# tick-box-1591A-mk-2_0.net
KiCad netlist of a schematic drawn in EAGLE
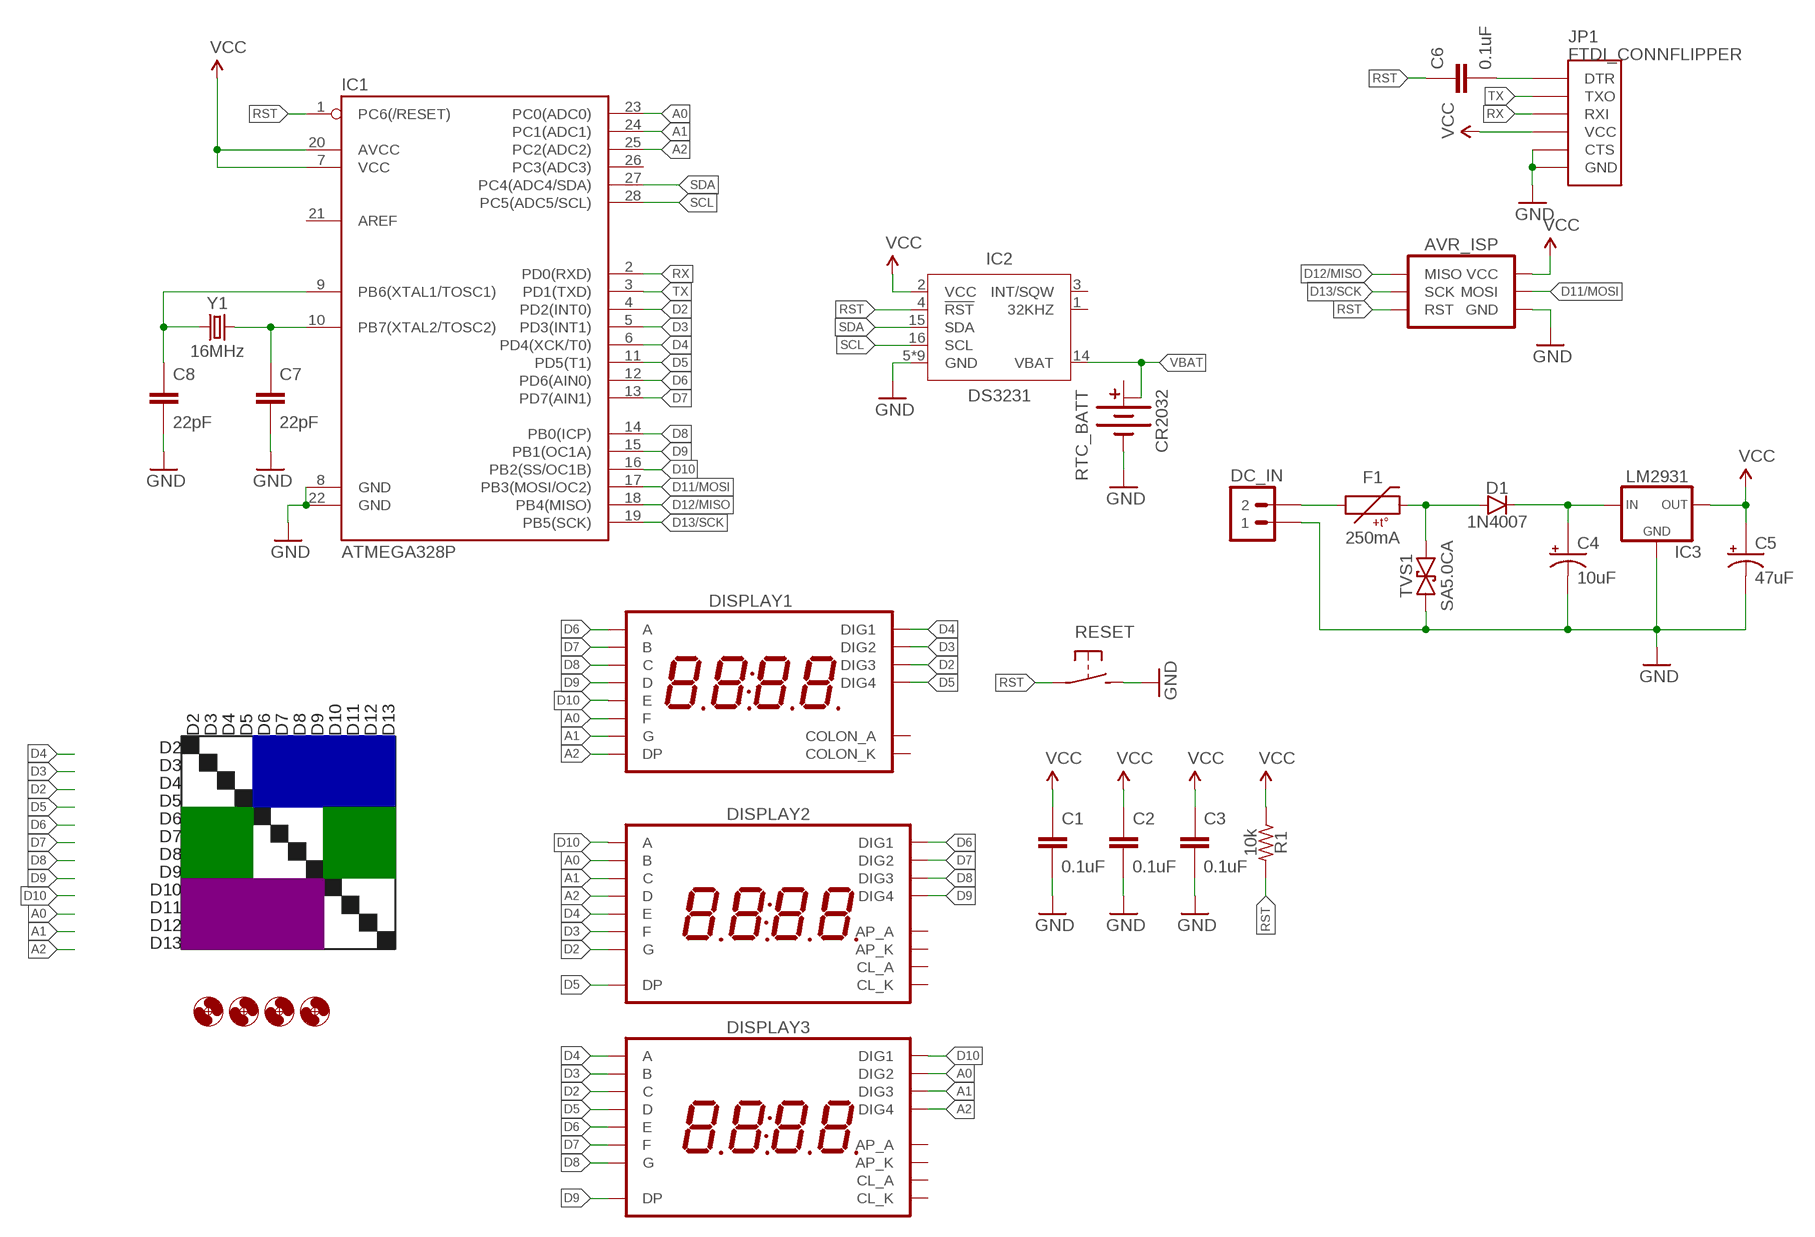
[diagram p0: schematic, sheet 1]

(export (version "E")
  (design (tool "Eeschema 10.0.6"))
  (components
    (comp (ref "AVR_ISP")
      (value "AVR_SPI_PRG_6PTH")
      (footprint "eagle-import:2X3")
      (libsource (lib "eagle-import") (part "AVR_SPI_PRG_6PTH"))
    )
    (comp (ref "C1")
      (value "0.1uF")
      (footprint "eagle-import:C025-024X044")
      (libsource (lib "eagle-import") (part "CAPACITOR-CERAMIC025-024X044"))
    )
    (comp (ref "C2")
      (value "0.1uF")
      (footprint "eagle-import:C025-024X044")
      (libsource (lib "eagle-import") (part "CAPACITOR-CERAMIC025-024X044"))
    )
    (comp (ref "C3")
      (value "0.1uF")
      (footprint "eagle-import:C025-024X044")
      (libsource (lib "eagle-import") (part "CAPACITOR-CERAMIC025-024X044"))
    )
    (comp (ref "C4")
      (value "10uF")
      (footprint "eagle-import:E2-4")
      (libsource (lib "eagle-import") (part "CAPACITOR-POLARIZEDE2-4"))
    )
    (comp (ref "C5")
      (value "47uF")
      (footprint "eagle-import:E2-4")
      (libsource (lib "eagle-import") (part "CAPACITOR-POLARIZEDE2-4"))
    )
    (comp (ref "C6")
      (value "0.1uF")
      (footprint "eagle-import:C025-024X044")
      (libsource (lib "eagle-import") (part "CAPACITOR-CERAMIC025-024X044"))
    )
    (comp (ref "C7")
      (value "22pF")
      (footprint "eagle-import:C025-024X044")
      (libsource (lib "eagle-import") (part "CAPACITOR-CERAMIC025-024X044"))
    )
    (comp (ref "C8")
      (value "22pF")
      (footprint "eagle-import:C025-024X044")
      (libsource (lib "eagle-import") (part "CAPACITOR-CERAMIC025-024X044"))
    )
    (comp (ref "D1")
      (value "1N4007")
      (footprint "eagle-import:DIODE-10.16MM")
      (libsource (lib "eagle-import") (part "DIODEPTH-10.68MM"))
    )
    (comp (ref "DC_IN")
      (value "M02PTH")
      (footprint "eagle-import:1X02")
      (libsource (lib "eagle-import") (part "M02PTH"))
    )
    (comp (ref "DISPLAY1")
      (value "7SEG_4DIGIT_COLON14.2MM-CC-NS")
      (footprint "eagle-import:7SEG_4DIG_NS")
      (libsource (lib "eagle-import") (part "7SEG_4DIGIT_COLON14.2MM-CC-NS"))
    )
    (comp (ref "DISPLAY2")
      (value "7SEG_4DIGIT_COLON_APOS")
      (footprint "eagle-import:7SEG_4DIG_10MM")
      (libsource (lib "eagle-import") (part "7SEG_4DIGIT_COLON_APOS"))
    )
    (comp (ref "DISPLAY3")
      (value "7SEG_4DIGIT_COLON_APOS")
      (footprint "eagle-import:7SEG_4DIG_10MM")
      (libsource (lib "eagle-import") (part "7SEG_4DIGIT_COLON_APOS"))
    )
    (comp (ref "F1")
      (value "250mA")
      (footprint "eagle-import:PTC-1206")
      (libsource (lib "eagle-import") (part "PTCSMD"))
    )
    (comp (ref "H1")
      (value "HOLE#2")
      (footprint "eagle-import:HOLE-#2")
      (libsource (lib "eagle-import") (part "HOLE#2"))
    )
    (comp (ref "H2")
      (value "HOLE#2")
      (footprint "eagle-import:HOLE-#2")
      (libsource (lib "eagle-import") (part "HOLE#2"))
    )
    (comp (ref "H3")
      (value "HOLE#2")
      (footprint "eagle-import:HOLE-#2")
      (libsource (lib "eagle-import") (part "HOLE#2"))
    )
    (comp (ref "H4")
      (value "HOLE#2")
      (footprint "eagle-import:HOLE-#2")
      (libsource (lib "eagle-import") (part "HOLE#2"))
    )
    (comp (ref "IC1")
      (value "ATMEGA328P")
      (footprint "eagle-import:DIL28-3")
      (libsource (lib "eagle-import") (part "ATMEGA328P_PDIP"))
    )
    (comp (ref "IC2")
      (value "DS3231")
      (footprint "eagle-import:SO16W")
      (libsource (lib "eagle-import") (part "DS3231"))
    )
    (comp (ref "IC3")
      (value "LM2931")
      (footprint "eagle-import:TO-92-AMMO")
      (libsource (lib "eagle-import") (part "V_REG_78XXTO-92-INLINE"))
    )
    (comp (ref "JP1")
      (value "FTDI_CONNFLIPPER")
      (footprint "eagle-import:FTDI_CONN_FLIP")
      (libsource (lib "eagle-import") (part "FTDI_CONNFLIPPER"))
    )
    (comp (ref "R1")
      (value "10k")
      (footprint "eagle-import:RESISTOR-AXIAL-PTH-6.35MM")
      (libsource (lib "eagle-import") (part "RESISTORPTH-AXIAL-6.35MM"))
    )
    (comp (ref "RESET")
      (value "SPST-NO-TACT3MM-PTH-SMALL-PADS")
      (footprint "eagle-import:DTS-3-SMALL-PADS")
      (libsource (lib "eagle-import") (part "SPST-NO-TACT3MM-PTH-SMALL-PADS"))
    )
    (comp (ref "RTC_BATT")
      (value "CR2032")
      (footprint "eagle-import:BATTCON_20MM_MINE")
      (libsource (lib "eagle-import") (part "BATTERY-COINCR2032_SMD"))
    )
    (comp (ref "TVS1")
      (value "SA5.0CA")
      (footprint "eagle-import:DO-41-TVS-BI-10.16MM")
      (libsource (lib "eagle-import") (part "TVSDO-41-10.16MM"))
    )
    (comp (ref "Y1")
      (value "16MHz")
      (footprint "eagle-import:HC49U-V")
      (libsource (lib "eagle-import") (part "CRYSTALHC49UV"))
    )
  )
  (nets
    (net (code "1") (name "A0") (class "Default")
      (node (ref "DISPLAY1") (pin "P$12") (pinfunction "F_P$12") (pintype "passive"))
      (node (ref "DISPLAY2") (pin "16") (pinfunction "B_16") (pintype "passive"))
      (node (ref "DISPLAY3") (pin "2") (pinfunction "DIG2_2") (pintype "passive"))
      (node (ref "IC1") (pin "23") (pinfunction "PC0(ADC0)_23") (pintype "bidirectional"))
    )
    (net (code "2") (name "A1") (class "Default")
      (node (ref "DISPLAY1") (pin "P$5") (pinfunction "G_P$5") (pintype "passive"))
      (node (ref "DISPLAY2") (pin "13") (pinfunction "C_13") (pintype "passive"))
      (node (ref "DISPLAY3") (pin "6") (pinfunction "DIG3_6") (pintype "passive"))
      (node (ref "IC1") (pin "24") (pinfunction "PC1(ADC1)_24") (pintype "bidirectional"))
    )
    (net (code "3") (name "A2") (class "Default")
      (node (ref "DISPLAY1") (pin "P$3") (pinfunction "DP_P$3") (pintype "passive"))
      (node (ref "DISPLAY2") (pin "3") (pinfunction "D_3") (pintype "passive"))
      (node (ref "DISPLAY3") (pin "8") (pinfunction "DIG4_8") (pintype "passive"))
      (node (ref "IC1") (pin "25") (pinfunction "PC2(ADC2)_25") (pintype "bidirectional"))
    )
    (net (code "4") (name "D2") (class "Default")
      (node (ref "DISPLAY1") (pin "P$10") (pinfunction "DIG3_P$10") (pintype "passive"))
      (node (ref "DISPLAY2") (pin "15") (pinfunction "G_15") (pintype "passive"))
      (node (ref "DISPLAY3") (pin "13") (pinfunction "C_13") (pintype "passive"))
      (node (ref "IC1") (pin "4") (pinfunction "PD2(INT0)_4") (pintype "bidirectional"))
    )
    (net (code "5") (name "D3") (class "Default")
      (node (ref "DISPLAY1") (pin "P$11") (pinfunction "DIG2_P$11") (pintype "passive"))
      (node (ref "DISPLAY2") (pin "11") (pinfunction "F_11") (pintype "passive"))
      (node (ref "DISPLAY3") (pin "16") (pinfunction "B_16") (pintype "passive"))
      (node (ref "IC1") (pin "5") (pinfunction "PD3(INT1)_5") (pintype "bidirectional"))
    )
    (net (code "6") (name "D4") (class "Default")
      (node (ref "DISPLAY1") (pin "P$14") (pinfunction "DIG1_P$14") (pintype "passive"))
      (node (ref "DISPLAY2") (pin "5") (pinfunction "E_5") (pintype "passive"))
      (node (ref "DISPLAY3") (pin "14") (pinfunction "A_14") (pintype "passive"))
      (node (ref "IC1") (pin "6") (pinfunction "PD4(XCK/T0)_6") (pintype "bidirectional"))
    )
    (net (code "7") (name "D5") (class "Default")
      (node (ref "DISPLAY1") (pin "P$6") (pinfunction "DIG4_P$6") (pintype "passive"))
      (node (ref "DISPLAY2") (pin "7") (pinfunction "DP_7") (pintype "passive"))
      (node (ref "DISPLAY3") (pin "3") (pinfunction "D_3") (pintype "passive"))
      (node (ref "IC1") (pin "11") (pinfunction "PD5(T1)_11") (pintype "bidirectional"))
    )
    (net (code "8") (name "D6") (class "Default")
      (node (ref "DISPLAY1") (pin "P$13") (pinfunction "A_P$13") (pintype "passive"))
      (node (ref "DISPLAY2") (pin "1") (pinfunction "DIG1_1") (pintype "passive"))
      (node (ref "DISPLAY3") (pin "5") (pinfunction "E_5") (pintype "passive"))
      (node (ref "IC1") (pin "12") (pinfunction "PD6(AIN0)_12") (pintype "bidirectional"))
    )
    (net (code "9") (name "D7") (class "Default")
      (node (ref "DISPLAY1") (pin "P$9") (pinfunction "B_P$9") (pintype "passive"))
      (node (ref "DISPLAY2") (pin "2") (pinfunction "DIG2_2") (pintype "passive"))
      (node (ref "DISPLAY3") (pin "11") (pinfunction "F_11") (pintype "passive"))
      (node (ref "IC1") (pin "13") (pinfunction "PD7(AIN1)_13") (pintype "bidirectional"))
    )
    (net (code "10") (name "D8") (class "Default")
      (node (ref "DISPLAY1") (pin "P$4") (pinfunction "C_P$4") (pintype "passive"))
      (node (ref "DISPLAY2") (pin "6") (pinfunction "DIG3_6") (pintype "passive"))
      (node (ref "DISPLAY3") (pin "15") (pinfunction "G_15") (pintype "passive"))
      (node (ref "IC1") (pin "14") (pinfunction "PB0(ICP)_14") (pintype "bidirectional"))
    )
    (net (code "11") (name "D9") (class "Default")
      (node (ref "DISPLAY1") (pin "P$2") (pinfunction "D_P$2") (pintype "passive"))
      (node (ref "DISPLAY2") (pin "8") (pinfunction "DIG4_8") (pintype "passive"))
      (node (ref "DISPLAY3") (pin "7") (pinfunction "DP_7") (pintype "passive"))
      (node (ref "IC1") (pin "15") (pinfunction "PB1(OC1A)_15") (pintype "bidirectional"))
    )
    (net (code "12") (name "D10") (class "Default")
      (node (ref "DISPLAY1") (pin "P$1") (pinfunction "E_P$1") (pintype "passive"))
      (node (ref "DISPLAY2") (pin "14") (pinfunction "A_14") (pintype "passive"))
      (node (ref "DISPLAY3") (pin "1") (pinfunction "DIG1_1") (pintype "passive"))
      (node (ref "IC1") (pin "16") (pinfunction "PB2(SS/OC1B)_16") (pintype "bidirectional"))
    )
    (net (code "13") (name "D11{slash}MOSI") (class "Default")
      (node (ref "AVR_ISP") (pin "4") (pinfunction "MOSI_4") (pintype "passive"))
      (node (ref "IC1") (pin "17") (pinfunction "PB3(MOSI/OC2)_17") (pintype "bidirectional"))
    )
    (net (code "14") (name "D12{slash}MISO") (class "Default")
      (node (ref "AVR_ISP") (pin "1") (pinfunction "MISO_1") (pintype "passive"))
      (node (ref "IC1") (pin "18") (pinfunction "PB4(MISO)_18") (pintype "bidirectional"))
    )
    (net (code "15") (name "D13{slash}SCK") (class "Default")
      (node (ref "AVR_ISP") (pin "3") (pinfunction "SCK_3") (pintype "passive"))
      (node (ref "IC1") (pin "19") (pinfunction "PB5(SCK)_19") (pintype "bidirectional"))
    )
    (net (code "16") (name "GND") (class "Default")
      (node (ref "AVR_ISP") (pin "6") (pinfunction "GND_6") (pintype "passive"))
      (node (ref "C1") (pin "2") (pinfunction "2_2") (pintype "passive"))
      (node (ref "C2") (pin "2") (pinfunction "2_2") (pintype "passive"))
      (node (ref "C3") (pin "2") (pinfunction "2_2") (pintype "passive"))
      (node (ref "C4") (pin "-") (pinfunction "-_-") (pintype "passive"))
      (node (ref "C5") (pin "-") (pinfunction "-_-") (pintype "passive"))
      (node (ref "C7") (pin "2") (pinfunction "2_2") (pintype "passive"))
      (node (ref "C8") (pin "2") (pinfunction "2_2") (pintype "passive"))
      (node (ref "DC_IN") (pin "1") (pinfunction "1_1") (pintype "passive"))
      (node (ref "IC1") (pin "22") (pinfunction "GND_22") (pintype "bidirectional"))
      (node (ref "IC1") (pin "8") (pinfunction "GND_8") (pintype "bidirectional"))
      (node (ref "IC2") (pin "10") (pinfunction "GND_10") (pintype "bidirectional"))
      (node (ref "IC2") (pin "11") (pinfunction "GND_11") (pintype "bidirectional"))
      (node (ref "IC2") (pin "12") (pinfunction "GND_12") (pintype "bidirectional"))
      (node (ref "IC2") (pin "13") (pinfunction "GND_13") (pintype "bidirectional"))
      (node (ref "IC2") (pin "5") (pinfunction "GND_5") (pintype "bidirectional"))
      (node (ref "IC2") (pin "6") (pinfunction "GND_6") (pintype "bidirectional"))
      (node (ref "IC2") (pin "7") (pinfunction "GND_7") (pintype "bidirectional"))
      (node (ref "IC2") (pin "8") (pinfunction "GND_8") (pintype "bidirectional"))
      (node (ref "IC2") (pin "9") (pinfunction "GND_9") (pintype "bidirectional"))
      (node (ref "IC3") (pin "2") (pinfunction "GND_2") (pintype "bidirectional"))
      (node (ref "JP1") (pin "CTS") (pinfunction "CTS_CTS") (pintype "bidirectional"))
      (node (ref "JP1") (pin "GND") (pinfunction "GND_GND") (pintype "bidirectional"))
      (node (ref "RESET") (pin "2") (pinfunction "2_2") (pintype "passive"))
      (node (ref "RTC_BATT") (pin "BOTTOM") (pinfunction "-_BOTTOM") (pintype "bidirectional"))
      (node (ref "TVS1") (pin "P$1") (pinfunction "1_P$1") (pintype "passive"))
    )
    (net (code "17") (name "Net-(C6-Pad2)") (class "Default")
      (node (ref "C6") (pin "2") (pinfunction "2_2") (pintype "passive"))
      (node (ref "JP1") (pin "DTR") (pinfunction "DTR_DTR") (pintype "bidirectional"))
    )
    (net (code "18") (name "Net-(DC_IN-Pad2)") (class "Default")
      (node (ref "DC_IN") (pin "2") (pinfunction "2_2") (pintype "passive"))
      (node (ref "F1") (pin "1") (pinfunction "1_1") (pintype "passive"))
    )
    (net (code "19") (name "Net-(IC1-PB6(XTAL1{slash}TOSC1))") (class "Default")
      (node (ref "C8") (pin "1") (pinfunction "1_1") (pintype "passive"))
      (node (ref "IC1") (pin "9") (pinfunction "PB6(XTAL1/TOSC1)_9") (pintype "bidirectional"))
      (node (ref "Y1") (pin "2") (pinfunction "2_2") (pintype "passive"))
    )
    (net (code "20") (name "Net-(IC1-PB7(XTAL2{slash}TOSC2))") (class "Default")
      (node (ref "C7") (pin "1") (pinfunction "1_1") (pintype "passive"))
      (node (ref "IC1") (pin "10") (pinfunction "PB7(XTAL2/TOSC2)_10") (pintype "bidirectional"))
      (node (ref "Y1") (pin "1") (pinfunction "1_1") (pintype "passive"))
    )
    (net (code "21") (name "Net-(IC3-IN)") (class "Default")
      (node (ref "C4") (pin "+") (pinfunction "+_+") (pintype "passive"))
      (node (ref "D1") (pin "C") (pinfunction "C_C") (pintype "passive"))
      (node (ref "IC3") (pin "1") (pinfunction "IN_1") (pintype "bidirectional"))
    )
    (net (code "22") (name "Net-(TVS1-2)") (class "Default")
      (node (ref "D1") (pin "A") (pinfunction "A_A") (pintype "passive"))
      (node (ref "F1") (pin "2") (pinfunction "2_2") (pintype "passive"))
      (node (ref "TVS1") (pin "P$2") (pinfunction "2_P$2") (pintype "passive"))
    )
    (net (code "23") (name "RST") (class "Default")
      (node (ref "AVR_ISP") (pin "5") (pinfunction "RST_5") (pintype "passive"))
      (node (ref "C6") (pin "1") (pinfunction "1_1") (pintype "passive"))
      (node (ref "IC1") (pin "1") (pinfunction "PC6(/RESET)_1") (pintype "bidirectional"))
      (node (ref "IC2") (pin "4") (pinfunction "~{RST}_4") (pintype "bidirectional"))
      (node (ref "R1") (pin "P$2") (pinfunction "2_P$2") (pintype "passive"))
      (node (ref "RESET") (pin "1") (pinfunction "1_1") (pintype "passive"))
    )
    (net (code "24") (name "RX") (class "Default")
      (node (ref "IC1") (pin "2") (pinfunction "PD0(RXD)_2") (pintype "bidirectional"))
      (node (ref "JP1") (pin "RXI") (pinfunction "RXI_RXI") (pintype "bidirectional"))
    )
    (net (code "25") (name "SCL") (class "Default")
      (node (ref "IC1") (pin "28") (pinfunction "PC5(ADC5/SCL)_28") (pintype "bidirectional"))
      (node (ref "IC2") (pin "16") (pinfunction "SCL_16") (pintype "bidirectional"))
    )
    (net (code "26") (name "SDA") (class "Default")
      (node (ref "IC1") (pin "27") (pinfunction "PC4(ADC4/SDA)_27") (pintype "bidirectional"))
      (node (ref "IC2") (pin "15") (pinfunction "SDA_15") (pintype "bidirectional"))
    )
    (net (code "27") (name "TX") (class "Default")
      (node (ref "IC1") (pin "3") (pinfunction "PD1(TXD)_3") (pintype "bidirectional"))
      (node (ref "JP1") (pin "TXO") (pinfunction "TXO_TXO") (pintype "bidirectional"))
    )
    (net (code "28") (name "VBAT") (class "Default")
      (node (ref "IC2") (pin "14") (pinfunction "VBAT_14") (pintype "bidirectional"))
      (node (ref "RTC_BATT") (pin "TOP@2") (pinfunction "+1_TOP@2") (pintype "bidirectional"))
    )
    (net (code "29") (name "VCC") (class "Default")
      (node (ref "AVR_ISP") (pin "2") (pinfunction "VCC_2") (pintype "passive"))
      (node (ref "C1") (pin "1") (pinfunction "1_1") (pintype "passive"))
      (node (ref "C2") (pin "1") (pinfunction "1_1") (pintype "passive"))
      (node (ref "C3") (pin "1") (pinfunction "1_1") (pintype "passive"))
      (node (ref "C5") (pin "+") (pinfunction "+_+") (pintype "passive"))
      (node (ref "IC1") (pin "20") (pinfunction "AVCC_20") (pintype "bidirectional"))
      (node (ref "IC1") (pin "7") (pinfunction "VCC_7") (pintype "bidirectional"))
      (node (ref "IC2") (pin "2") (pinfunction "VCC_2") (pintype "bidirectional"))
      (node (ref "IC3") (pin "3") (pinfunction "OUT_3") (pintype "bidirectional"))
      (node (ref "JP1") (pin "VCC") (pinfunction "VCC_VCC") (pintype "bidirectional"))
      (node (ref "R1") (pin "P$1") (pinfunction "1_P$1") (pintype "passive"))
    )
    (net (code "30") (name "unconnected-(DISPLAY1-COLON_A-PadP$8)") (class "Default")
      (node (ref "DISPLAY1") (pin "P$8") (pinfunction "COLON_A_P$8") (pintype "passive"))
    )
    (net (code "31") (name "unconnected-(DISPLAY1-COLON_K-PadP$7)") (class "Default")
      (node (ref "DISPLAY1") (pin "P$7") (pinfunction "COLON_K_P$7") (pintype "passive"))
    )
    (net (code "32") (name "unconnected-(DISPLAY2-AP_A-Pad10)") (class "Default")
      (node (ref "DISPLAY2") (pin "10") (pinfunction "AP_A_10") (pintype "bidirectional"))
    )
    (net (code "33") (name "unconnected-(DISPLAY2-AP_K-Pad9)") (class "Default")
      (node (ref "DISPLAY2") (pin "9") (pinfunction "AP_K_9") (pintype "bidirectional"))
    )
    (net (code "34") (name "unconnected-(DISPLAY2-CL_A-Pad4)") (class "Default")
      (node (ref "DISPLAY2") (pin "4") (pinfunction "CL_A_4") (pintype "passive"))
    )
    (net (code "35") (name "unconnected-(DISPLAY2-CL_K-Pad12)") (class "Default")
      (node (ref "DISPLAY2") (pin "12") (pinfunction "CL_K_12") (pintype "passive"))
    )
    (net (code "36") (name "unconnected-(DISPLAY3-AP_A-Pad10)") (class "Default")
      (node (ref "DISPLAY3") (pin "10") (pinfunction "AP_A_10") (pintype "bidirectional"))
    )
    (net (code "37") (name "unconnected-(DISPLAY3-AP_K-Pad9)") (class "Default")
      (node (ref "DISPLAY3") (pin "9") (pinfunction "AP_K_9") (pintype "bidirectional"))
    )
    (net (code "38") (name "unconnected-(DISPLAY3-CL_A-Pad4)") (class "Default")
      (node (ref "DISPLAY3") (pin "4") (pinfunction "CL_A_4") (pintype "passive"))
    )
    (net (code "39") (name "unconnected-(DISPLAY3-CL_K-Pad12)") (class "Default")
      (node (ref "DISPLAY3") (pin "12") (pinfunction "CL_K_12") (pintype "passive"))
    )
    (net (code "40") (name "unconnected-(IC1-AREF-Pad21)") (class "Default")
      (node (ref "IC1") (pin "21") (pinfunction "AREF_21") (pintype "bidirectional"))
    )
    (net (code "41") (name "unconnected-(IC1-PC3(ADC3)-Pad26)") (class "Default")
      (node (ref "IC1") (pin "26") (pinfunction "PC3(ADC3)_26") (pintype "bidirectional"))
    )
    (net (code "42") (name "unconnected-(IC2-32KHZ-Pad1)") (class "Default")
      (node (ref "IC2") (pin "1") (pinfunction "32KHZ_1") (pintype "bidirectional"))
    )
    (net (code "43") (name "unconnected-(IC2-INT{slash}SQW-Pad3)") (class "Default")
      (node (ref "IC2") (pin "3") (pinfunction "INT/SQW_3") (pintype "bidirectional"))
    )
    (net (code "44") (name "unconnected-(RTC_BATT-+-PadTOP@1)") (class "Default")
      (node (ref "RTC_BATT") (pin "TOP@1") (pinfunction "+_TOP@1") (pintype "bidirectional"))
    )
  )
)
